# 03_POWER.net
KiCad netlist of a schematic drawn in Altium Designer
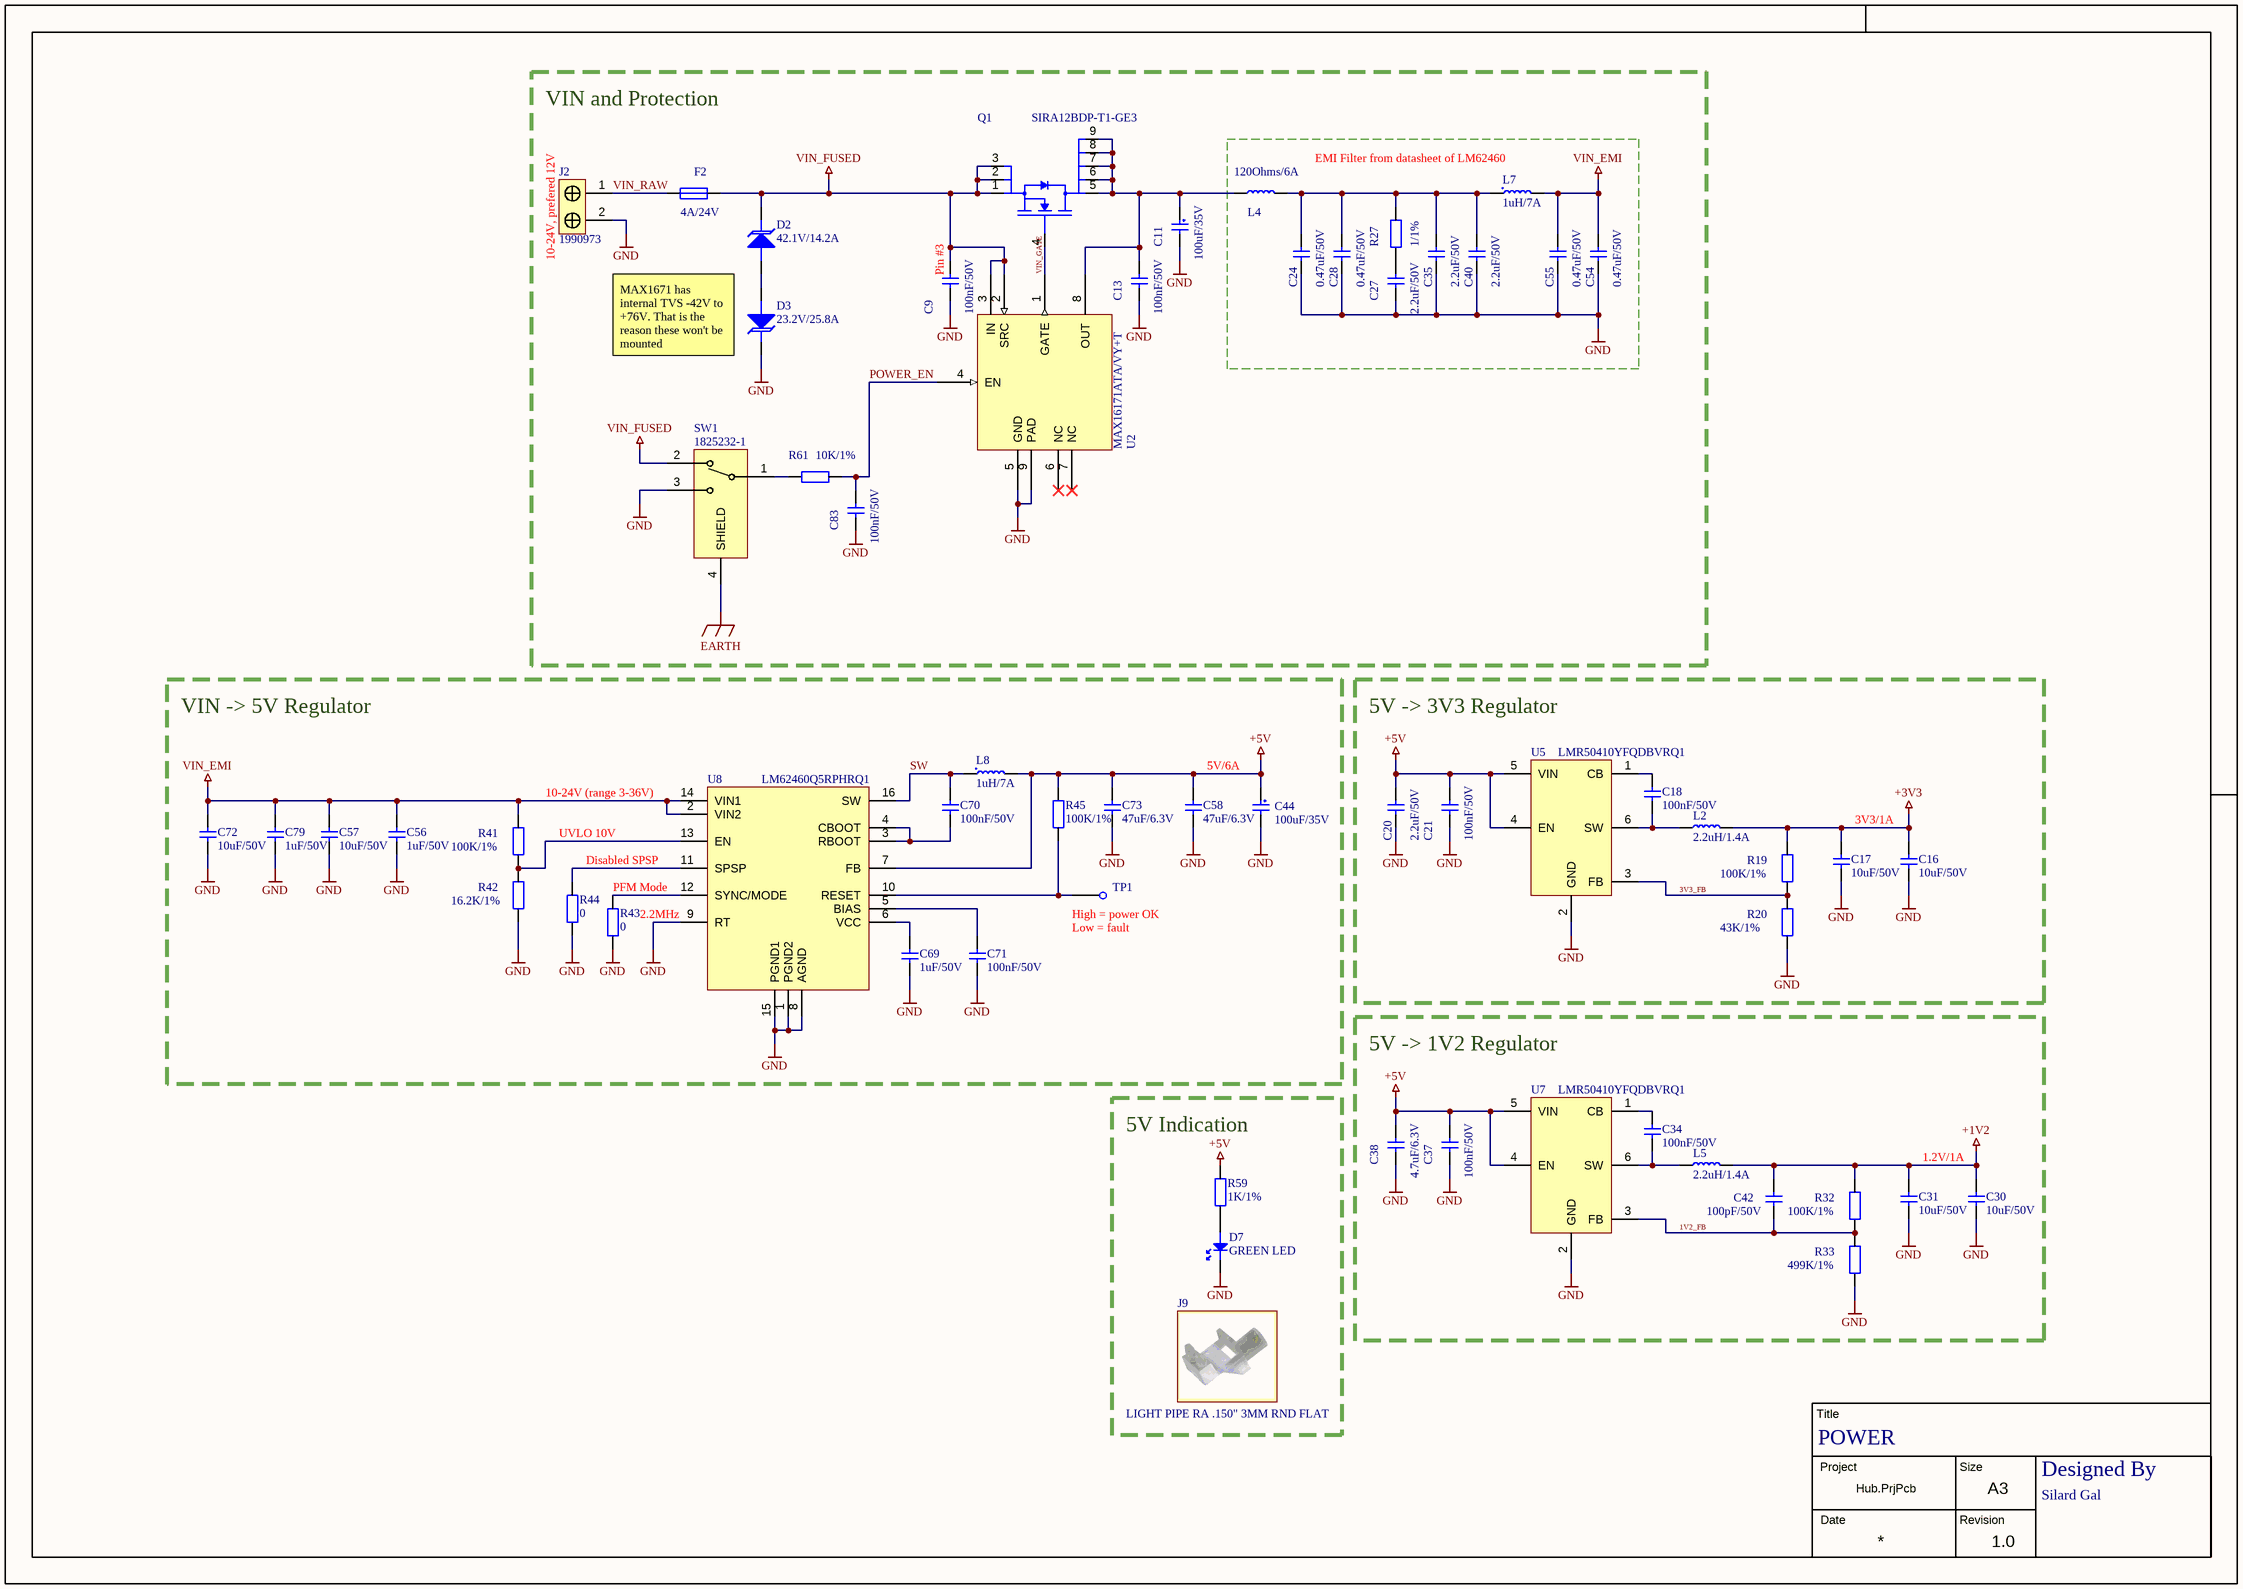
[diagram p0: 03 POWER.SchDoc]

(export (version "E")
  (design (tool "Eeschema 10.0.6"))
  (components
    (comp (ref "C9")
      (value "100nF/50V")
      (footprint "CAPC1005X06N")
      (description "0.1 µF ±10% 50V Ceramic Capacitor X7R 0402 (1005 Metric)")
      (fields
        (field (name "MANUFACTURER") "Murata Electronics")
        (field (name "MFR_PART_NUMBER") "GCM155R71H104KE02J")
      )
      (libsource (lib "altium_symbol") (part "GCM155R71H104KE02J"))
    )
    (comp (ref "C11")
      (value "100uF/35V")
      (footprint "CAPAE11580X70M")
      (description "100 µF 35 V Aluminum - Polymer Capacitors Radial, Can - SMD 2000 Hrs @ 125°C")
      (fields (field (name "MANUFACTURER") "KEMET") (field (name "MFR_PART_NUMBER") "A769KE107M1VLAS031"))
      (libsource (lib "altium_symbol") (part "A769KE107M1VLAS031"))
    )
    (comp (ref "C13")
      (value "100nF/50V")
      (footprint "CAPC1005X06N")
      (description "0.1 µF ±10% 50V Ceramic Capacitor X7R 0402 (1005 Metric)")
      (fields
        (field (name "MANUFACTURER") "Murata Electronics")
        (field (name "MFR_PART_NUMBER") "GCM155R71H104KE02J")
      )
      (libsource (lib "altium_symbol") (part "GCM155R71H104KE02J"))
    )
    (comp (ref "C16")
      (value "10uF/50V")
      (footprint "CAPC3216X18N")
      (description "10 µF ±20% 50V Ceramic Capacitor X5R 1206 (3216 Metric)")
      (fields
        (field (name "MANUFACTURER") "Murata Electronics")
        (field (name "MFR_PART_NUMBER") "GRT31CR61H106ME01L")
      )
      (libsource (lib "altium_symbol") (part "GRT31CR61H106ME01L"))
    )
    (comp (ref "C17")
      (value "10uF/50V")
      (footprint "CAPC3216X18N")
      (description "10 µF ±20% 50V Ceramic Capacitor X5R 1206 (3216 Metric)")
      (fields
        (field (name "MANUFACTURER") "Murata Electronics")
        (field (name "MFR_PART_NUMBER") "GRT31CR61H106ME01L")
      )
      (libsource (lib "altium_symbol") (part "GRT31CR61H106ME01L"))
    )
    (comp (ref "C18")
      (value "100nF/50V")
      (footprint "CAPC1005X06N")
      (description "0.1 µF ±10% 50V Ceramic Capacitor X7R 0402 (1005 Metric)")
      (fields
        (field (name "MANUFACTURER") "Murata Electronics")
        (field (name "MFR_PART_NUMBER") "GCM155R71H104KE02J")
      )
      (libsource (lib "altium_symbol") (part "GCM155R71H104KE02J"))
    )
    (comp (ref "C20")
      (value "2.2uF/50V")
      (footprint "INDC1608X10N")
      (description "2.2 µF ±20% 50V Ceramic Capacitor X5R 0603 (1608 Metric)")
      (fields
        (field (name "MANUFACTURER") "Murata Electronics")
        (field (name "MFR_PART_NUMBER") "GRT188R61H225ME13D")
      )
      (libsource (lib "altium_symbol") (part "GRT188R61H225ME13D"))
    )
    (comp (ref "C21")
      (value "100nF/50V")
      (footprint "CAPC1005X06N")
      (description "0.1 µF ±10% 50V Ceramic Capacitor X7R 0402 (1005 Metric)")
      (fields
        (field (name "MANUFACTURER") "Murata Electronics")
        (field (name "MFR_PART_NUMBER") "GCM155R71H104KE02J")
      )
      (libsource (lib "altium_symbol") (part "GCM155R71H104KE02J"))
    )
    (comp (ref "C24")
      (value "0.47uF/50V")
      (footprint "INDC1608X10N")
      (description "0.47 µF ±10% 50V Ceramic Capacitor X7R 0603 (1608 Metric)")
      (fields
        (field (name "MANUFACTURER") "TDK Corporation")
        (field (name "MFR_PART_NUMBER") "CGA3E3X7R1H474K080AB")
      )
      (libsource (lib "altium_symbol") (part "CGA3E3X7R1H474K080AB"))
    )
    (comp (ref "C27")
      (value "2.2uF/50V")
      (footprint "INDC1608X10N")
      (description "2.2 µF ±20% 50V Ceramic Capacitor X5R 0603 (1608 Metric)")
      (fields
        (field (name "MANUFACTURER") "Murata Electronics")
        (field (name "MFR_PART_NUMBER") "GRT188R61H225ME13D")
      )
      (libsource (lib "altium_symbol") (part "GRT188R61H225ME13D"))
    )
    (comp (ref "C28")
      (value "0.47uF/50V")
      (footprint "INDC1608X10N")
      (description "0.47 µF ±10% 50V Ceramic Capacitor X7R 0603 (1608 Metric)")
      (fields
        (field (name "MANUFACTURER") "TDK Corporation")
        (field (name "MFR_PART_NUMBER") "CGA3E3X7R1H474K080AB")
      )
      (libsource (lib "altium_symbol") (part "CGA3E3X7R1H474K080AB"))
    )
    (comp (ref "C30")
      (value "10uF/50V")
      (footprint "CAPC3216X18N")
      (description "10 µF ±20% 50V Ceramic Capacitor X5R 1206 (3216 Metric)")
      (fields
        (field (name "MANUFACTURER") "Murata Electronics")
        (field (name "MFR_PART_NUMBER") "GRT31CR61H106ME01L")
      )
      (libsource (lib "altium_symbol") (part "GRT31CR61H106ME01L"))
    )
    (comp (ref "C31")
      (value "10uF/50V")
      (footprint "CAPC3216X18N")
      (description "10 µF ±20% 50V Ceramic Capacitor X5R 1206 (3216 Metric)")
      (fields
        (field (name "MANUFACTURER") "Murata Electronics")
        (field (name "MFR_PART_NUMBER") "GRT31CR61H106ME01L")
      )
      (libsource (lib "altium_symbol") (part "GRT31CR61H106ME01L"))
    )
    (comp (ref "C34")
      (value "100nF/50V")
      (footprint "CAPC1005X06N")
      (description "0.1 µF ±10% 50V Ceramic Capacitor X7R 0402 (1005 Metric)")
      (fields
        (field (name "MANUFACTURER") "Murata Electronics")
        (field (name "MFR_PART_NUMBER") "GCM155R71H104KE02J")
      )
      (libsource (lib "altium_symbol") (part "GCM155R71H104KE02J"))
    )
    (comp (ref "C35")
      (value "2.2uF/50V")
      (footprint "INDC1608X10N")
      (description "2.2 µF ±20% 50V Ceramic Capacitor X5R 0603 (1608 Metric)")
      (fields
        (field (name "MANUFACTURER") "Murata Electronics")
        (field (name "MFR_PART_NUMBER") "GRT188R61H225ME13D")
      )
      (libsource (lib "altium_symbol") (part "GRT188R61H225ME13D"))
    )
    (comp (ref "C37")
      (value "100nF/50V")
      (footprint "CAPC1005X06N")
      (description "0.1 µF ±10% 50V Ceramic Capacitor X7R 0402 (1005 Metric)")
      (fields
        (field (name "MANUFACTURER") "Murata Electronics")
        (field (name "MFR_PART_NUMBER") "GCM155R71H104KE02J")
      )
      (libsource (lib "altium_symbol") (part "GCM155R71H104KE02J"))
    )
    (comp (ref "C38")
      (value "4.7uF/6.3V")
      (footprint "CAPC1005X06N")
      (description "4.7 µF ±20% 6.3V Ceramic Capacitor X5R 0402 (1005 Metric)")
      (fields (field (name "MANUFACTURER") "Taiyo Yuden") (field (name "MFR_PART_NUMBER") "JMK105BBJ475MVHF"))
      (libsource (lib "altium_symbol") (part "JMK105BBJ475MVHF"))
    )
    (comp (ref "C40")
      (value "2.2uF/50V")
      (footprint "INDC1608X10N")
      (description "2.2 µF ±20% 50V Ceramic Capacitor X5R 0603 (1608 Metric)")
      (fields
        (field (name "MANUFACTURER") "Murata Electronics")
        (field (name "MFR_PART_NUMBER") "GRT188R61H225ME13D")
      )
      (libsource (lib "altium_symbol") (part "GRT188R61H225ME13D"))
    )
    (comp (ref "C42")
      (value "100pF/50V")
      (footprint "CAPC1005X06N")
      (description "100 pF ±5% 50V Ceramic Capacitor C0G, NP0 0402 (1005 Metric)")
      (fields
        (field (name "MANUFACTURER") "Murata Electronics")
        (field (name "MFR_PART_NUMBER") "GCM1555C1H101JA16D")
      )
      (libsource (lib "altium_symbol") (part "GCM1555C1H101JA16D"))
    )
    (comp (ref "C44")
      (value "100uF/35V")
      (footprint "CAPAE11580X70M")
      (description "100 µF 35 V Aluminum - Polymer Capacitors Radial, Can - SMD 2000 Hrs @ 125°C")
      (fields (field (name "MANUFACTURER") "KEMET") (field (name "MFR_PART_NUMBER") "A769KE107M1VLAS031"))
      (libsource (lib "altium_symbol") (part "A769KE107M1VLAS031"))
    )
    (comp (ref "C54")
      (value "0.47uF/50V")
      (footprint "INDC1608X10N")
      (description "0.47 µF ±10% 50V Ceramic Capacitor X7R 0603 (1608 Metric)")
      (fields
        (field (name "MANUFACTURER") "TDK Corporation")
        (field (name "MFR_PART_NUMBER") "CGA3E3X7R1H474K080AB")
      )
      (libsource (lib "altium_symbol") (part "CGA3E3X7R1H474K080AB"))
    )
    (comp (ref "C55")
      (value "0.47uF/50V")
      (footprint "INDC1608X10N")
      (description "0.47 µF ±10% 50V Ceramic Capacitor X7R 0603 (1608 Metric)")
      (fields
        (field (name "MANUFACTURER") "TDK Corporation")
        (field (name "MFR_PART_NUMBER") "CGA3E3X7R1H474K080AB")
      )
      (libsource (lib "altium_symbol") (part "CGA3E3X7R1H474K080AB"))
    )
    (comp (ref "C56")
      (value "1uF/50V")
      (footprint "INDC1608X10N")
      (description "1 µF ±10% 50V Ceramic Capacitor X5R 0603 (1608 Metric)")
      (fields
        (field (name "MANUFACTURER") "Murata Electronics")
        (field (name "MFR_PART_NUMBER") "GRT188R61H105KE13D")
      )
      (libsource (lib "altium_symbol") (part "GRT188R61H105KE13D"))
    )
    (comp (ref "C57")
      (value "10uF/50V")
      (footprint "CAPC3216X18N")
      (description "10 µF ±20% 50V Ceramic Capacitor X5R 1206 (3216 Metric)")
      (fields
        (field (name "MANUFACTURER") "Murata Electronics")
        (field (name "MFR_PART_NUMBER") "GRT31CR61H106ME01L")
      )
      (libsource (lib "altium_symbol") (part "GRT31CR61H106ME01L"))
    )
    (comp (ref "C58")
      (value "47uF/6.3V")
      (footprint "INDC1608X10N")
      (description "47 µF ±20% 6.3V Ceramic Capacitor X5R 0603 (1608 Metric)")
      (fields
        (field (name "MANUFACTURER") "Murata Electronics")
        (field (name "MFR_PART_NUMBER") "GRM188R60J476ME15D")
      )
      (libsource (lib "altium_symbol") (part "GRM188R60J476ME15D"))
    )
    (comp (ref "C69")
      (value "1uF/50V")
      (footprint "INDC1608X10N")
      (description "1 µF ±10% 50V Ceramic Capacitor X5R 0603 (1608 Metric)")
      (fields
        (field (name "MANUFACTURER") "Murata Electronics")
        (field (name "MFR_PART_NUMBER") "GRT188R61H105KE13D")
      )
      (libsource (lib "altium_symbol") (part "GRT188R61H105KE13D"))
    )
    (comp (ref "C70")
      (value "100nF/50V")
      (footprint "CAPC1005X06N")
      (description "0.1 µF ±10% 50V Ceramic Capacitor X7R 0402 (1005 Metric)")
      (fields
        (field (name "MANUFACTURER") "Murata Electronics")
        (field (name "MFR_PART_NUMBER") "GCM155R71H104KE02J")
      )
      (libsource (lib "altium_symbol") (part "GCM155R71H104KE02J"))
    )
    (comp (ref "C71")
      (value "100nF/50V")
      (footprint "CAPC1005X06N")
      (description "0.1 µF ±10% 50V Ceramic Capacitor X7R 0402 (1005 Metric)")
      (fields
        (field (name "MANUFACTURER") "Murata Electronics")
        (field (name "MFR_PART_NUMBER") "GCM155R71H104KE02J")
      )
      (libsource (lib "altium_symbol") (part "GCM155R71H104KE02J"))
    )
    (comp (ref "C72")
      (value "10uF/50V")
      (footprint "CAPC3216X18N")
      (description "10 µF ±20% 50V Ceramic Capacitor X5R 1206 (3216 Metric)")
      (fields
        (field (name "MANUFACTURER") "Murata Electronics")
        (field (name "MFR_PART_NUMBER") "GRT31CR61H106ME01L")
      )
      (libsource (lib "altium_symbol") (part "GRT31CR61H106ME01L"))
    )
    (comp (ref "C73")
      (value "47uF/6.3V")
      (footprint "INDC1608X10N")
      (description "47 µF ±20% 6.3V Ceramic Capacitor X5R 0603 (1608 Metric)")
      (fields
        (field (name "MANUFACTURER") "Murata Electronics")
        (field (name "MFR_PART_NUMBER") "GRM188R60J476ME15D")
      )
      (libsource (lib "altium_symbol") (part "GRM188R60J476ME15D"))
    )
    (comp (ref "C79")
      (value "1uF/50V")
      (footprint "INDC1608X10N")
      (description "1 µF ±10% 50V Ceramic Capacitor X5R 0603 (1608 Metric)")
      (fields
        (field (name "MANUFACTURER") "Murata Electronics")
        (field (name "MFR_PART_NUMBER") "GRT188R61H105KE13D")
      )
      (libsource (lib "altium_symbol") (part "GRT188R61H105KE13D"))
    )
    (comp (ref "C83")
      (value "100nF/50V")
      (footprint "CAPC1005X06N")
      (description "0.1 µF ±10% 50V Ceramic Capacitor X7R 0402 (1005 Metric)")
      (fields
        (field (name "MANUFACTURER") "Murata Electronics")
        (field (name "MFR_PART_NUMBER") "GCM155R71H104KE02J")
      )
      (libsource (lib "altium_symbol") (part "GCM155R71H104KE02J"))
    )
    (comp (ref "D2")
      (value "42.1V/14.2A")
      (footprint "DIOM4739X26N")
      (description "42.1V Clamp 14.2A Ipp Tvs Diode Surface Mount SMB")
      (fields
        (field (name "MANUFACTURER") "Diodes Incorporated")
        (field (name "MFR_PART_NUMBER") "SMBJ26A-13-F")
      )
      (libsource (lib "altium_symbol") (part "SMBJ26A-13-F"))
    )
    (comp (ref "D3")
      (value "23.2V/25.8A")
      (footprint "DIOM4739X26N")
      (description "23.2V Clamp 25.8A Ipp Tvs Diode Surface Mount SMB")
      (fields
        (field (name "MANUFACTURER") "Diodes Incorporated")
        (field (name "MFR_PART_NUMBER") "SMBJ14A-13-F")
      )
      (libsource (lib "altium_symbol") (part "SMBJ14A-13-F"))
    )
    (comp (ref "D7")
      (value "GREEN LED")
      (footprint "DIOC1608X06L")
      (description "White 0402 Light Emitting Diodes (LED) RoHS")
      (fields (field (name "MANUFACTURER") "Lite-On Inc.") (field (name "MFR_PART_NUMBER") "LTST-C191KGKT"))
      (libsource (lib "altium_symbol") (part "LTST-C191KGKT"))
    )
    (comp (ref "F2")
      (value "4A/24V")
      (footprint "INDC7451X08N")
      (description "Polymeric PTC Resettable Fuse 24V 2 A Ih Surface Mount 2920 (7351 Metric), Concave - 4A trip")
      (fields (field (name "MANUFACTURER") "Bel Fuse Inc.") (field (name "MFR_PART_NUMBER") "0ZCF0200AF2C"))
      (libsource (lib "altium_symbol") (part "0ZCF0200AF2C"))
    )
    (comp (ref "J2")
      (value "1990973")
      (footprint "1990973")
      (description "2 Position Wire to Board Terminal Block Horizontal with Board 0.197\" (5.00mm) Through Hole")
      (fields (field (name "MANUFACTURER") "Phoenix Contact"))
      (libsource (lib "altium_symbol") (part "1990973"))
    )
    (comp (ref "J9")
      (value "LIGHT PIPE RA .150\" 3MM RND FLAT")
      (footprint "SLP3-150-150-F")
      (description "Light Pipe Single Clear Rigid Board Mount, Press Fit, Right Angle")
      (fields (field (name "MANUFACTURER") "Bivar Inc.") (field (name "MFR_PART_NUMBER") "SLP3-150-150-F"))
      (libsource (lib "altium_symbol") (part "SLP3-150-150-F"))
    )
    (comp (ref "L2")
      (value "2.2uH/1.4A")
      (footprint "INDP2016X12N")
      (description "2.2 µH Shielded Drum Core, Wirewound Inductor 1.4 A 180mOhm Max 0806 (2016 Metric)")
      (fields
        (field (name "MANUFACTURER") "Laird-Signal Integrity Products")
        (field (name "MFR_PART_NUMBER") "TYA2016102R2M-10")
      )
      (libsource (lib "altium_symbol") (part "TYA2016102R2M-10"))
    )
    (comp (ref "L4")
      (value "120Ohms/6A")
      (footprint "INDC3216X18N")
      (description "120 Ohms @ 100 MHz 1 Power Line Ferrite Bead 1206 (3216 Metric) 6A 9mOhm")
      (fields
        (field (name "MANUFACTURER") "Murata Electronics")
        (field (name "MFR_PART_NUMBER") "BLM31KN121SN1L")
      )
      (libsource (lib "altium_symbol") (part "BLM31KN121SN1L"))
    )
    (comp (ref "L5")
      (value "2.2uH/1.4A")
      (footprint "INDP2016X12N")
      (description "2.2 µH Shielded Drum Core, Wirewound Inductor 1.4 A 180mOhm Max 0806 (2016 Metric)")
      (fields
        (field (name "MANUFACTURER") "Laird-Signal Integrity Products")
        (field (name "MFR_PART_NUMBER") "TYA2016102R2M-10")
      )
      (libsource (lib "altium_symbol") (part "TYA2016102R2M-10"))
    )
    (comp (ref "L7")
      (value "1uH/7A")
      (footprint "INDP5752X20N")
      (description "1 µH Shielded Drum Core, Wirewound Inductor 7 A 20mOhm Max Nonstandard")
      (fields (field (name "MANUFACTURER") "Bourns Inc.") (field (name "MFR_PART_NUMBER") "SRP5020TA-1R0M"))
      (libsource (lib "altium_symbol") (part "SRP5020TA-1R0M"))
    )
    (comp (ref "L8")
      (value "1uH/7A")
      (footprint "INDP5752X20N")
      (description "1 µH Shielded Drum Core, Wirewound Inductor 7 A 20mOhm Max Nonstandard")
      (fields (field (name "MANUFACTURER") "Bourns Inc.") (field (name "MFR_PART_NUMBER") "SRP5020TA-1R0M"))
      (libsource (lib "altium_symbol") (part "SRP5020TA-1R0M"))
    )
    (comp (ref "Q1")
      (value "SIRA12BDP-T1-GE3")
      (footprint "POWERPAK-SO-8-Single")
      (description "N-Channel 30 V 27A (Ta), 60A (Tc) 5W (Ta), 38W (Tc) Surface Mount PowerPAK® SO-8")
      (fields (field (name "MANUFACTURER") "Vishay Siliconix"))
      (libsource (lib "altium_symbol") (part "SIRA12BDP-T1-GE3"))
    )
    (comp (ref "R19")
      (value "100K/1%")
      (footprint "RESC1005X04N")
      (description "100 kOhms ±1% 0.063W, 1/16W Chip Resistor 0402 (1005 Metric) Automotive AEC-Q200 Thick Film")
      (fields
        (field (name "MANUFACTURER") "Stackpole Electronics Inc")
        (field (name "MFR_PART_NUMBER") "RMCF0402FT100K")
      )
      (libsource (lib "altium_symbol") (part "RMCF0402FT100K"))
    )
    (comp (ref "R20")
      (value "43K/1%")
      (footprint "RESC1005X04N")
      (description "43 kOhms ±1% 0.1W, 1/10W Chip Resistor 0402 (1005 Metric) Automotive AEC-Q200 Thick Film")
      (fields
        (field (name "MANUFACTURER") "Panasonic Electronic Components")
        (field (name "MFR_PART_NUMBER") "ERJ-2RKF4302X")
      )
      (libsource (lib "altium_symbol") (part "ERJ-2RKF4302X"))
    )
    (comp (ref "R27")
      (value "1/1%")
      (footprint "RESC1608X04N")
      (description "1 Ohms ±1% 0.1W, 1/10W Chip Resistor 0603 (1608 Metric) Automotive AEC-Q200 Thick Film")
      (fields
        (field (name "MANUFACTURER") "Stackpole Electronics Inc")
        (field (name "MFR_PART_NUMBER") "RMCF0603FT1R00")
      )
      (libsource (lib "altium_symbol") (part "RMCF0603FT1R00"))
    )
    (comp (ref "R32")
      (value "100K/1%")
      (footprint "RESC1005X04N")
      (description "100 kOhms ±1% 0.063W, 1/16W Chip Resistor 0402 (1005 Metric) Automotive AEC-Q200 Thick Film")
      (fields
        (field (name "MANUFACTURER") "Stackpole Electronics Inc")
        (field (name "MFR_PART_NUMBER") "RMCF0402FT100K")
      )
      (libsource (lib "altium_symbol") (part "RMCF0402FT100K"))
    )
    (comp (ref "R33")
      (value "499K/1%")
      (footprint "RESC1005X04N")
      (description "499 kOhms ±1% 0.063W, 1/16W Chip Resistor 0402 (1005 Metric) Automotive AEC-Q200 Thick Film")
      (fields
        (field (name "MANUFACTURER") "Stackpole Electronics Inc")
        (field (name "MFR_PART_NUMBER") "RMCF0402FT499K")
      )
      (libsource (lib "altium_symbol") (part "RMCF0402FT499K"))
    )
    (comp (ref "R41")
      (value "100K/1%")
      (footprint "RESC1005X04N")
      (description "100 kOhms ±1% 0.063W, 1/16W Chip Resistor 0402 (1005 Metric) Automotive AEC-Q200 Thick Film")
      (fields
        (field (name "MANUFACTURER") "Stackpole Electronics Inc")
        (field (name "MFR_PART_NUMBER") "RMCF0402FT100K")
      )
      (libsource (lib "altium_symbol") (part "RMCF0402FT100K"))
    )
    (comp (ref "R42")
      (value "16.2K/1%")
      (footprint "RESC1005X04N")
      (description "16.2 kOhms ±1% 0.1W, 1/10W Chip Resistor 0402 (1005 Metric) Automotive AEC-Q200 Thick Film")
      (fields
        (field (name "MANUFACTURER") "Panasonic Electronic Components")
        (field (name "MFR_PART_NUMBER") "ERJ-2RKF1622X")
      )
      (libsource (lib "altium_symbol") (part "ERJ-2RKF1622X"))
    )
    (comp (ref "R43")
      (value "0")
      (footprint "RESC1005X04N")
      (fields
        (field (name "MANUFACTURER") "UNI-ROYAL(Uniroyal Elec)")
        (field (name "MFR_PART_NUMBER") "0402WGF0000TCE")
      )
      (libsource (lib "altium_symbol") (part "0402WGF0000TCE"))
    )
    (comp (ref "R44")
      (value "0")
      (footprint "RESC1005X04N")
      (fields
        (field (name "MANUFACTURER") "UNI-ROYAL(Uniroyal Elec)")
        (field (name "MFR_PART_NUMBER") "0402WGF0000TCE")
      )
      (libsource (lib "altium_symbol") (part "0402WGF0000TCE"))
    )
    (comp (ref "R45")
      (value "100K/1%")
      (footprint "RESC1005X04N")
      (description "100 kOhms ±1% 0.063W, 1/16W Chip Resistor 0402 (1005 Metric) Automotive AEC-Q200 Thick Film")
      (fields
        (field (name "MANUFACTURER") "Stackpole Electronics Inc")
        (field (name "MFR_PART_NUMBER") "RMCF0402FT100K")
      )
      (libsource (lib "altium_symbol") (part "RMCF0402FT100K"))
    )
    (comp (ref "R59")
      (value "1K/1%")
      (footprint "RESC1005X04N")
      (description "1 kOhms ±1% 0.063W, 1/16W Chip Resistor 0402 (1005 Metric) Automotive AEC-Q200 Thick Film")
      (fields
        (field (name "MANUFACTURER") "Stackpole Electronics Inc")
        (field (name "MFR_PART_NUMBER") "RMCF0402FT1K00")
      )
      (libsource (lib "altium_symbol") (part "RMCF0402FT1K00"))
    )
    (comp (ref "R61")
      (value "10K/1%")
      (footprint "RESC1005X04N")
      (description "10 kOhms ±1% 0.063W, 1/16W Chip Resistor 0402 (1005 Metric) Automotive AEC-Q200 Thick Film")
      (fields
        (field (name "MANUFACTURER") "Stackpole Electronics Inc")
        (field (name "MFR_PART_NUMBER") "RMCF0402FT10K0")
      )
      (libsource (lib "altium_symbol") (part "RMCF0402FT10K0"))
    )
    (comp (ref "SW1")
      (value "1825232-1")
      (footprint "1825232-1")
      (description "Slide Switch SPDT Through Hole, Right Angle")
      (fields (field (name "MANUFACTURER") "TE Connectivity ALCOSWITCH Switches"))
      (libsource (lib "altium_symbol") (part "1825232-1"))
    )
    (comp (ref "TP1")
      (value "Test Point 1mm")
      (footprint "TEST_POINT_1mm")
      (libsource (lib "altium_symbol") (part "TestPoint"))
    )
    (comp (ref "U2")
      (value "MAX16171ATA/VY+T")
      (footprint "PSON50P300X80_HS-9N")
      (description "OR Controller N+1 ORing Controller N-Channel 1:1 8-TDFN-CU (2x3)")
      (fields (field (name "MANUFACTURER") "Analog Devices Inc./Maxim Integrated"))
      (libsource (lib "altium_symbol") (part "MAX16171ATA/VY+T"))
    )
    (comp (ref "U5")
      (value "LMR50410YFQDBVRQ1")
      (footprint "SOT95P280X145-6N")
      (description "Buck Switching Regulator IC Positive Adjustable 1V 1 Output 1A SOT-23-6")
      (fields (field (name "MANUFACTURER") "Texas Instruments"))
      (libsource (lib "altium_symbol") (part "LMR50410YFQDBVRQ1"))
    )
    (comp (ref "U7")
      (value "LMR50410YFQDBVRQ1")
      (footprint "SOT95P280X145-6N")
      (description "Buck Switching Regulator IC Positive Adjustable 1V 1 Output 1A SOT-23-6")
      (fields (field (name "MANUFACTURER") "Texas Instruments"))
      (libsource (lib "altium_symbol") (part "LMR50410YFQDBVRQ1"))
    )
    (comp (ref "U8")
      (value "LM62460Q5RPHRQ1")
      (footprint "VQFN-HR")
      (description "Switching Voltage Regulators 6-A automotive buck converter optimized for power density and low EMI")
      (fields (field (name "MANUFACTURER") "Texas Instruments"))
      (libsource (lib "altium_symbol") (part "LM62460Q5RPHRQ1"))
    )
  )
  (nets
    (net (code "1") (name "+1V2") (class "Default")
      (node (ref "C30") (pin "2") (pinfunction "2_2") (pintype "passive"))
      (node (ref "C31") (pin "2") (pinfunction "2_2") (pintype "passive"))
      (node (ref "C42") (pin "2") (pinfunction "2_2") (pintype "passive"))
      (node (ref "L5") (pin "2") (pinfunction "2_2") (pintype "passive"))
      (node (ref "R32") (pin "2") (pinfunction "2_2") (pintype "passive"))
    )
    (net (code "2") (name "+3V3") (class "Default")
      (node (ref "C16") (pin "2") (pinfunction "2_2") (pintype "passive"))
      (node (ref "C17") (pin "2") (pinfunction "2_2") (pintype "passive"))
      (node (ref "L2") (pin "2") (pinfunction "2_2") (pintype "passive"))
      (node (ref "R19") (pin "2") (pinfunction "2_2") (pintype "passive"))
    )
    (net (code "3") (name "+5V") (class "Default")
      (node (ref "C20") (pin "2") (pinfunction "2_2") (pintype "passive"))
      (node (ref "C21") (pin "2") (pinfunction "2_2") (pintype "passive"))
      (node (ref "C37") (pin "2") (pinfunction "2_2") (pintype "passive"))
      (node (ref "C38") (pin "2") (pinfunction "2_2") (pintype "passive"))
      (node (ref "C44") (pin "1") (pinfunction "1_1") (pintype "passive"))
      (node (ref "C58") (pin "2") (pinfunction "2_2") (pintype "passive"))
      (node (ref "C73") (pin "2") (pinfunction "2_2") (pintype "passive"))
      (node (ref "L8") (pin "2") (pinfunction "2_2") (pintype "passive"))
      (node (ref "R45") (pin "1") (pinfunction "1_1") (pintype "passive"))
      (node (ref "R59") (pin "2") (pinfunction "2_2") (pintype "passive"))
      (node (ref "U5") (pin "4") (pinfunction "EN_4") (pintype "passive"))
      (node (ref "U5") (pin "5") (pinfunction "VIN_5") (pintype "passive"))
      (node (ref "U7") (pin "4") (pinfunction "EN_4") (pintype "passive"))
      (node (ref "U7") (pin "5") (pinfunction "VIN_5") (pintype "passive"))
      (node (ref "U8") (pin "7") (pinfunction "FB_7") (pintype "passive"))
    )
    (net (code "4") (name "/1V2_FB") (class "Default")
      (node (ref "C42") (pin "1") (pinfunction "1_1") (pintype "passive"))
      (node (ref "R32") (pin "1") (pinfunction "1_1") (pintype "passive"))
      (node (ref "R33") (pin "2") (pinfunction "2_2") (pintype "passive"))
      (node (ref "U7") (pin "3") (pinfunction "FB_3") (pintype "passive"))
    )
    (net (code "5") (name "/3V3_FB") (class "Default")
      (node (ref "R19") (pin "1") (pinfunction "1_1") (pintype "passive"))
      (node (ref "R20") (pin "2") (pinfunction "2_2") (pintype "passive"))
      (node (ref "U5") (pin "3") (pinfunction "FB_3") (pintype "passive"))
    )
    (net (code "6") (name "/POWER_EN") (class "Default")
      (node (ref "C83") (pin "2") (pinfunction "2_2") (pintype "passive"))
      (node (ref "R61") (pin "2") (pinfunction "2_2") (pintype "passive"))
      (node (ref "U2") (pin "4") (pinfunction "EN_4") (pintype "input"))
    )
    (net (code "7") (name "/SW") (class "Default")
      (node (ref "C70") (pin "2") (pinfunction "2_2") (pintype "passive"))
      (node (ref "L8") (pin "1") (pinfunction "1_1") (pintype "passive"))
      (node (ref "U8") (pin "16") (pinfunction "SW_16") (pintype "passive"))
    )
    (net (code "8") (name "/VIN_GATE") (class "Default")
      (node (ref "Q1") (pin "4") (pinfunction "4_4") (pintype "passive"))
      (node (ref "U2") (pin "1") (pinfunction "GATE_1") (pintype "output"))
    )
    (net (code "9") (name "/VIN_RAW") (class "Default")
      (node (ref "F2") (pin "1") (pinfunction "1_1") (pintype "passive"))
      (node (ref "J2") (pin "1") (pintype "passive"))
    )
    (net (code "10") (name "EARTH") (class "Default")
      (node (ref "SW1") (pin "4") (pinfunction "SHIELD_4") (pintype "passive"))
    )
    (net (code "11") (name "GND") (class "Default")
      (node (ref "C11") (pin "2") (pinfunction "2_2") (pintype "passive"))
      (node (ref "C13") (pin "1") (pinfunction "1_1") (pintype "passive"))
      (node (ref "C16") (pin "1") (pinfunction "1_1") (pintype "passive"))
      (node (ref "C17") (pin "1") (pinfunction "1_1") (pintype "passive"))
      (node (ref "C20") (pin "1") (pinfunction "1_1") (pintype "passive"))
      (node (ref "C21") (pin "1") (pinfunction "1_1") (pintype "passive"))
      (node (ref "C24") (pin "1") (pinfunction "1_1") (pintype "passive"))
      (node (ref "C27") (pin "1") (pinfunction "1_1") (pintype "passive"))
      (node (ref "C28") (pin "1") (pinfunction "1_1") (pintype "passive"))
      (node (ref "C30") (pin "1") (pinfunction "1_1") (pintype "passive"))
      (node (ref "C31") (pin "1") (pinfunction "1_1") (pintype "passive"))
      (node (ref "C35") (pin "1") (pinfunction "1_1") (pintype "passive"))
      (node (ref "C37") (pin "1") (pinfunction "1_1") (pintype "passive"))
      (node (ref "C38") (pin "1") (pinfunction "1_1") (pintype "passive"))
      (node (ref "C40") (pin "1") (pinfunction "1_1") (pintype "passive"))
      (node (ref "C44") (pin "2") (pinfunction "2_2") (pintype "passive"))
      (node (ref "C54") (pin "1") (pinfunction "1_1") (pintype "passive"))
      (node (ref "C55") (pin "1") (pinfunction "1_1") (pintype "passive"))
      (node (ref "C56") (pin "1") (pinfunction "1_1") (pintype "passive"))
      (node (ref "C57") (pin "1") (pinfunction "1_1") (pintype "passive"))
      (node (ref "C58") (pin "1") (pinfunction "1_1") (pintype "passive"))
      (node (ref "C69") (pin "1") (pinfunction "1_1") (pintype "passive"))
      (node (ref "C71") (pin "1") (pinfunction "1_1") (pintype "passive"))
      (node (ref "C72") (pin "1") (pinfunction "1_1") (pintype "passive"))
      (node (ref "C73") (pin "1") (pinfunction "1_1") (pintype "passive"))
      (node (ref "C79") (pin "1") (pinfunction "1_1") (pintype "passive"))
      (node (ref "C83") (pin "1") (pinfunction "1_1") (pintype "passive"))
      (node (ref "C9") (pin "1") (pinfunction "1_1") (pintype "passive"))
      (node (ref "D3") (pin "1") (pintype "passive"))
      (node (ref "D7") (pin "1") (pinfunction "1_1") (pintype "passive"))
      (node (ref "J2") (pin "2") (pintype "passive"))
      (node (ref "R20") (pin "1") (pinfunction "1_1") (pintype "passive"))
      (node (ref "R33") (pin "1") (pinfunction "1_1") (pintype "passive"))
      (node (ref "R42") (pin "1") (pinfunction "1_1") (pintype "passive"))
      (node (ref "R43") (pin "1") (pinfunction "1_1") (pintype "passive"))
      (node (ref "R44") (pin "1") (pinfunction "1_1") (pintype "passive"))
      (node (ref "SW1") (pin "3") (pinfunction "3_3") (pintype "passive"))
      (node (ref "U2") (pin "5") (pinfunction "GND_5") (pintype "power_in"))
      (node (ref "U2") (pin "9") (pinfunction "PAD_9") (pintype "power_in"))
      (node (ref "U5") (pin "2") (pinfunction "GND_2") (pintype "passive"))
      (node (ref "U7") (pin "2") (pinfunction "GND_2") (pintype "passive"))
      (node (ref "U8") (pin "1") (pinfunction "PGND2_1") (pintype "passive"))
      (node (ref "U8") (pin "15") (pinfunction "PGND1_15") (pintype "passive"))
      (node (ref "U8") (pin "8") (pinfunction "AGND_8") (pintype "passive"))
      (node (ref "U8") (pin "9") (pinfunction "RT_9") (pintype "passive"))
    )
    (net (code "12") (name "Net-(C24-Pad2)") (class "Default")
      (node (ref "C24") (pin "2") (pinfunction "2_2") (pintype "passive"))
      (node (ref "C28") (pin "2") (pinfunction "2_2") (pintype "passive"))
      (node (ref "C35") (pin "2") (pinfunction "2_2") (pintype "passive"))
      (node (ref "C40") (pin "2") (pinfunction "2_2") (pintype "passive"))
      (node (ref "L4") (pin "2") (pinfunction "2_2") (pintype "passive"))
      (node (ref "L7") (pin "1") (pinfunction "1_1") (pintype "passive"))
      (node (ref "R27") (pin "2") (pinfunction "2_2") (pintype "passive"))
    )
    (net (code "13") (name "Net-(C27-Pad2)") (class "Default")
      (node (ref "C27") (pin "2") (pinfunction "2_2") (pintype "passive"))
      (node (ref "R27") (pin "1") (pinfunction "1_1") (pintype "passive"))
    )
    (net (code "14") (name "Net-(D2-Pad2)") (class "Default")
      (node (ref "D2") (pin "2") (pintype "passive"))
      (node (ref "D3") (pin "2") (pintype "passive"))
    )
    (net (code "15") (name "Net-(D7-Pad2)") (class "Default")
      (node (ref "D7") (pin "2") (pinfunction "2_2") (pintype "passive"))
      (node (ref "R59") (pin "1") (pinfunction "1_1") (pintype "passive"))
    )
    (net (code "16") (name "Net-(R61-Pad1)") (class "Default")
      (node (ref "R61") (pin "1") (pinfunction "1_1") (pintype "passive"))
      (node (ref "SW1") (pin "1") (pinfunction "1_1") (pintype "passive"))
    )
    (net (code "17") (name "Net-(U2-OUT)") (class "Default")
      (node (ref "C11") (pin "1") (pinfunction "1_1") (pintype "passive"))
      (node (ref "C13") (pin "2") (pinfunction "2_2") (pintype "passive"))
      (node (ref "L4") (pin "1") (pinfunction "1_1") (pintype "passive"))
      (node (ref "Q1") (pin "5") (pinfunction "5_5") (pintype "passive"))
      (node (ref "Q1") (pin "6") (pinfunction "6_6") (pintype "passive"))
      (node (ref "Q1") (pin "7") (pinfunction "7_7") (pintype "passive"))
      (node (ref "Q1") (pin "8") (pinfunction "8_8") (pintype "passive"))
      (node (ref "Q1") (pin "9") (pinfunction "9_9") (pintype "passive"))
      (node (ref "U2") (pin "8") (pinfunction "OUT_8") (pintype "power_in"))
    )
    (net (code "18") (name "Net-(U5-CB)") (class "Default")
      (node (ref "C18") (pin "2") (pinfunction "2_2") (pintype "passive"))
      (node (ref "U5") (pin "1") (pinfunction "CB_1") (pintype "passive"))
    )
    (net (code "19") (name "Net-(U5-SW)") (class "Default")
      (node (ref "C18") (pin "1") (pinfunction "1_1") (pintype "passive"))
      (node (ref "L2") (pin "1") (pinfunction "1_1") (pintype "passive"))
      (node (ref "U5") (pin "6") (pinfunction "SW_6") (pintype "passive"))
    )
    (net (code "20") (name "Net-(U7-CB)") (class "Default")
      (node (ref "C34") (pin "2") (pinfunction "2_2") (pintype "passive"))
      (node (ref "U7") (pin "1") (pinfunction "CB_1") (pintype "passive"))
    )
    (net (code "21") (name "Net-(U7-SW)") (class "Default")
      (node (ref "C34") (pin "1") (pinfunction "1_1") (pintype "passive"))
      (node (ref "L5") (pin "1") (pinfunction "1_1") (pintype "passive"))
      (node (ref "U7") (pin "6") (pinfunction "SW_6") (pintype "passive"))
    )
    (net (code "22") (name "Net-(U8-BIAS)") (class "Default")
      (node (ref "C71") (pin "2") (pinfunction "2_2") (pintype "passive"))
      (node (ref "U8") (pin "5") (pinfunction "BIAS_5") (pintype "passive"))
    )
    (net (code "23") (name "Net-(U8-CBOOT)") (class "Default")
      (node (ref "C70") (pin "1") (pinfunction "1_1") (pintype "passive"))
      (node (ref "U8") (pin "3") (pinfunction "RBOOT_3") (pintype "passive"))
      (node (ref "U8") (pin "4") (pinfunction "CBOOT_4") (pintype "passive"))
    )
    (net (code "24") (name "Net-(U8-EN)") (class "Default")
      (node (ref "R41") (pin "1") (pinfunction "1_1") (pintype "passive"))
      (node (ref "R42") (pin "2") (pinfunction "2_2") (pintype "passive"))
      (node (ref "U8") (pin "13") (pinfunction "EN_13") (pintype "passive"))
    )
    (net (code "25") (name "Net-(U8-RESET)") (class "Default")
      (node (ref "R45") (pin "2") (pinfunction "2_2") (pintype "passive"))
      (node (ref "TP1") (pin "1") (pinfunction "1_1") (pintype "passive"))
      (node (ref "U8") (pin "10") (pinfunction "RESET_10") (pintype "passive"))
    )
    (net (code "26") (name "Net-(U8-SPSP)") (class "Default")
      (node (ref "R44") (pin "2") (pinfunction "2_2") (pintype "passive"))
      (node (ref "U8") (pin "11") (pinfunction "SPSP_11") (pintype "passive"))
    )
    (net (code "27") (name "Net-(U8-SYNC{slash}MODE)") (class "Default")
      (node (ref "R43") (pin "2") (pinfunction "2_2") (pintype "passive"))
      (node (ref "U8") (pin "12") (pinfunction "SYNC/MODE_12") (pintype "passive"))
    )
    (net (code "28") (name "Net-(U8-VCC)") (class "Default")
      (node (ref "C69") (pin "2") (pinfunction "2_2") (pintype "passive"))
      (node (ref "U8") (pin "6") (pinfunction "VCC_6") (pintype "passive"))
    )
    (net (code "29") (name "VIN_EMI") (class "Default")
      (node (ref "C54") (pin "2") (pinfunction "2_2") (pintype "passive"))
      (node (ref "C55") (pin "2") (pinfunction "2_2") (pintype "passive"))
      (node (ref "C56") (pin "2") (pinfunction "2_2") (pintype "passive"))
      (node (ref "C57") (pin "2") (pinfunction "2_2") (pintype "passive"))
      (node (ref "C72") (pin "2") (pinfunction "2_2") (pintype "passive"))
      (node (ref "C79") (pin "2") (pinfunction "2_2") (pintype "passive"))
      (node (ref "L7") (pin "2") (pinfunction "2_2") (pintype "passive"))
      (node (ref "R41") (pin "2") (pinfunction "2_2") (pintype "passive"))
      (node (ref "U8") (pin "14") (pinfunction "VIN1_14") (pintype "passive"))
      (node (ref "U8") (pin "2") (pinfunction "VIN2_2") (pintype "passive"))
    )
    (net (code "30") (name "VIN_FUSED") (class "Default")
      (node (ref "C9") (pin "2") (pinfunction "2_2") (pintype "passive"))
      (node (ref "D2") (pin "1") (pintype "passive"))
      (node (ref "F2") (pin "2") (pinfunction "2_2") (pintype "passive"))
      (node (ref "Q1") (pin "1") (pinfunction "1_1") (pintype "passive"))
      (node (ref "Q1") (pin "2") (pinfunction "2_2") (pintype "passive"))
      (node (ref "Q1") (pin "3") (pinfunction "3_3") (pintype "passive"))
      (node (ref "SW1") (pin "2") (pinfunction "2_2") (pintype "passive"))
      (node (ref "U2") (pin "2") (pinfunction "SRC_2") (pintype "input"))
      (node (ref "U2") (pin "3") (pinfunction "IN_3") (pintype "power_in"))
    )
    (net (code "31") (name "unconnected-(U2-NC-Pad6)") (class "Default")
      (node (ref "U2") (pin "6") (pinfunction "NC_6") (pintype "passive+no_connect"))
    )
    (net (code "32") (name "unconnected-(U2-NC-Pad7)") (class "Default")
      (node (ref "U2") (pin "7") (pinfunction "NC_7") (pintype "passive+no_connect"))
    )
  )
)
